# lb_uno_v1_3.net
KiCad netlist of a schematic drawn in EAGLE
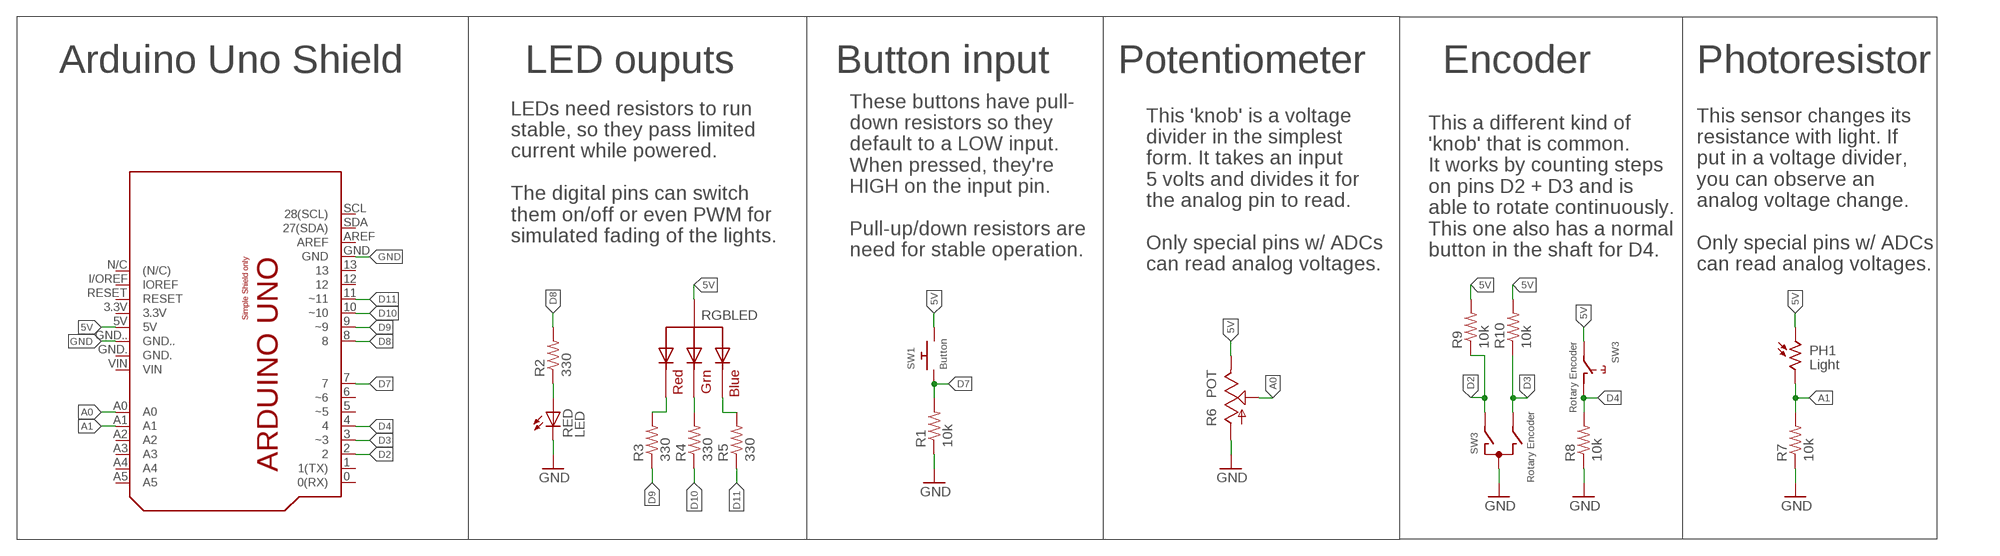
[diagram p0: schematic, sheet 1]

(export (version "E")
  (design (tool "Eeschema 10.0.6"))
  (components
    (comp (ref "PCB1")
      (value "ARDUINO_UNO_V2")
      (footprint "eagle-import:ARDUINO_UNO_V2")
      (libsource (lib "eagle-import") (part "ARDUINO_UNO_V2"))
    )
    (comp (ref "PH1")
      (value "Light")
      (footprint "eagle-import:T0-46-A10XX")
      (libsource (lib "eagle-import") (part "A1060_12"))
    )
    (comp (ref "R1")
      (value "10k")
      (footprint "eagle-import:0207_9")
      (libsource (lib "eagle-import") (part "R-US_0207/9"))
    )
    (comp (ref "R2")
      (value "330")
      (footprint "eagle-import:0207_9")
      (libsource (lib "eagle-import") (part "R-US_0207/9"))
    )
    (comp (ref "R3")
      (value "330")
      (footprint "eagle-import:0207_9")
      (libsource (lib "eagle-import") (part "R-US_0207/9"))
    )
    (comp (ref "R4")
      (value "330")
      (footprint "eagle-import:0207_9")
      (libsource (lib "eagle-import") (part "R-US_0207/9"))
    )
    (comp (ref "R5")
      (value "330")
      (footprint "eagle-import:0207_9")
      (libsource (lib "eagle-import") (part "R-US_0207/9"))
    )
    (comp (ref "R6")
      (value "POT")
      (footprint "eagle-import:B25P")
      (libsource (lib "eagle-import") (part "TRIM_US-B25P"))
    )
    (comp (ref "R7")
      (value "10k")
      (footprint "eagle-import:0207_9")
      (libsource (lib "eagle-import") (part "R-US_0207/9"))
    )
    (comp (ref "R8")
      (value "10k")
      (footprint "eagle-import:0207_9")
      (libsource (lib "eagle-import") (part "R-US_0207/9"))
    )
    (comp (ref "R9")
      (value "10k")
      (footprint "eagle-import:0207_9")
      (libsource (lib "eagle-import") (part "R-US_0207/9"))
    )
    (comp (ref "R10")
      (value "10k")
      (footprint "eagle-import:0207_9")
      (libsource (lib "eagle-import") (part "R-US_0207/9"))
    )
    (comp (ref "RED")
      (value "LED")
      (footprint "eagle-import:5MM")
      (libsource (lib "eagle-import") (part "LED5MM"))
    )
    (comp (ref "RGBLED")
      (value "RGBLED")
      (footprint "eagle-import:LED5MMRGB")
      (libsource (lib "eagle-import") (part "RGBLED_CA-5MM"))
    )
    (comp (ref "SW1")
      (value "Button")
      (footprint "eagle-import:TACT_PANA-EVQ")
      (libsource (lib "eagle-import") (part "SWITCH_PUSHBUTTONEVQ-PE"))
    )
    (comp (ref "SW3")
      (value "Rotary Encoder")
      (footprint "eagle-import:ALPS_EC12E_SW")
      (fields (field (name "MPN") "EC12E2424407"))
      (libsource (lib "eagle-import") (part "EC12E_SW"))
    )
  )
  (nets
    (net (code "1") (name "5V") (class "Default")
      (node (ref "PCB1") (pin "5V") (pinfunction "5V_5V") (pintype "bidirectional"))
      (node (ref "PH1") (pin "1") (pinfunction "1_1") (pintype "passive"))
      (node (ref "R10") (pin "2") (pinfunction "2_2") (pintype "passive"))
      (node (ref "R6") (pin "E") (pinfunction "E_E") (pintype "passive"))
      (node (ref "R9") (pin "2") (pinfunction "2_2") (pintype "passive"))
      (node (ref "RGBLED") (pin "2") (pinfunction "VCC_2") (pintype "bidirectional"))
      (node (ref "SW1") (pin "P$2") (pinfunction "P$2_P$2") (pintype "passive"))
      (node (ref "SW3") (pin "E") (pinfunction "2_E") (pintype "passive"))
    )
    (net (code "2") (name "A0") (class "Default")
      (node (ref "PCB1") (pin "A0") (pinfunction "A0_A0") (pintype "bidirectional"))
      (node (ref "R6") (pin "S") (pinfunction "S_S") (pintype "passive"))
    )
    (net (code "3") (name "A1") (class "Default")
      (node (ref "PCB1") (pin "A1") (pinfunction "A1_A1") (pintype "bidirectional"))
      (node (ref "PH1") (pin "2") (pinfunction "2_2") (pintype "passive"))
      (node (ref "R7") (pin "2") (pinfunction "2_2") (pintype "passive"))
    )
    (net (code "4") (name "D2") (class "Default")
      (node (ref "PCB1") (pin "2") (pinfunction "2_2") (pintype "bidirectional"))
      (node (ref "R9") (pin "1") (pinfunction "1_1") (pintype "passive"))
      (node (ref "SW3") (pin "A") (pinfunction "A_A") (pintype "passive"))
    )
    (net (code "5") (name "D3") (class "Default")
      (node (ref "PCB1") (pin "3") (pinfunction "~{3}_3") (pintype "bidirectional"))
      (node (ref "R10") (pin "1") (pinfunction "1_1") (pintype "passive"))
      (node (ref "SW3") (pin "B") (pinfunction "B_B") (pintype "passive"))
    )
    (net (code "6") (name "D4") (class "Default")
      (node (ref "PCB1") (pin "4") (pinfunction "4_4") (pintype "bidirectional"))
      (node (ref "R8") (pin "2") (pinfunction "2_2") (pintype "passive"))
      (node (ref "SW3") (pin "D") (pinfunction "1_D") (pintype "passive"))
    )
    (net (code "7") (name "D7") (class "Default")
      (node (ref "PCB1") (pin "7") (pinfunction "7_7") (pintype "bidirectional"))
      (node (ref "R1") (pin "2") (pinfunction "2_2") (pintype "passive"))
      (node (ref "SW1") (pin "P$1") (pinfunction "P$1_P$1") (pintype "passive"))
    )
    (net (code "8") (name "D8") (class "Default")
      (node (ref "PCB1") (pin "8") (pinfunction "8_8") (pintype "bidirectional"))
      (node (ref "R2") (pin "2") (pinfunction "2_2") (pintype "passive"))
    )
    (net (code "9") (name "D9") (class "Default")
      (node (ref "PCB1") (pin "9") (pinfunction "~{9}_9") (pintype "bidirectional"))
      (node (ref "R3") (pin "1") (pinfunction "1_1") (pintype "passive"))
    )
    (net (code "10") (name "D10") (class "Default")
      (node (ref "PCB1") (pin "10") (pinfunction "~{10}_10") (pintype "bidirectional"))
      (node (ref "R4") (pin "1") (pinfunction "1_1") (pintype "passive"))
    )
    (net (code "11") (name "D11") (class "Default")
      (node (ref "PCB1") (pin "11") (pinfunction "~{11}_11") (pintype "bidirectional"))
      (node (ref "R5") (pin "1") (pinfunction "1_1") (pintype "passive"))
    )
    (net (code "12") (name "GND") (class "Default")
      (node (ref "PCB1") (pin "GND") (pinfunction "GND_GND") (pintype "bidirectional"))
      (node (ref "PCB1") (pin "GND..") (pinfunction "GND.._GND..") (pintype "bidirectional"))
      (node (ref "R1") (pin "1") (pinfunction "1_1") (pintype "passive"))
      (node (ref "R6") (pin "A") (pinfunction "A_A") (pintype "passive"))
      (node (ref "R7") (pin "1") (pinfunction "1_1") (pintype "passive"))
      (node (ref "R8") (pin "1") (pinfunction "1_1") (pintype "passive"))
      (node (ref "RED") (pin "OUT") (pinfunction "C_OUT") (pintype "passive"))
      (node (ref "SW3") (pin "C") (pinfunction "C_C") (pintype "passive"))
    )
    (net (code "13") (name "Net-(RED-A)") (class "Default")
      (node (ref "R2") (pin "1") (pinfunction "1_1") (pintype "passive"))
      (node (ref "RED") (pin "IN") (pinfunction "A_IN") (pintype "passive"))
    )
    (net (code "14") (name "Net-(RGBLED-BLUE)") (class "Default")
      (node (ref "R5") (pin "2") (pinfunction "2_2") (pintype "passive"))
      (node (ref "RGBLED") (pin "4") (pinfunction "BLUE_4") (pintype "bidirectional"))
    )
    (net (code "15") (name "Net-(RGBLED-GREEN)") (class "Default")
      (node (ref "R4") (pin "2") (pinfunction "2_2") (pintype "passive"))
      (node (ref "RGBLED") (pin "3") (pinfunction "GREEN_3") (pintype "bidirectional"))
    )
    (net (code "16") (name "Net-(RGBLED-RED)") (class "Default")
      (node (ref "R3") (pin "2") (pinfunction "2_2") (pintype "passive"))
      (node (ref "RGBLED") (pin "1") (pinfunction "RED_1") (pintype "bidirectional"))
    )
    (net (code "17") (name "unconnected-(PCB1-(N{slash}C)-PadN{slash}C)") (class "Default")
      (node (ref "PCB1") (pin "N/C") (pinfunction "(N/C)_N/C") (pintype "bidirectional"))
    )
    (net (code "18") (name "unconnected-(PCB1-0(RX)-Pad0)") (class "Default")
      (node (ref "PCB1") (pin "0") (pinfunction "0(RX)_0") (pintype "bidirectional"))
    )
    (net (code "19") (name "unconnected-(PCB1-1(TX)-Pad1)") (class "Default")
      (node (ref "PCB1") (pin "1") (pinfunction "1(TX)_1") (pintype "bidirectional"))
    )
    (net (code "20") (name "unconnected-(PCB1-27(SDA)-PadSDA)") (class "Default")
      (node (ref "PCB1") (pin "SDA") (pinfunction "27(SDA)_SDA") (pintype "bidirectional"))
    )
    (net (code "21") (name "unconnected-(PCB1-28(SCL)-PadSCL)") (class "Default")
      (node (ref "PCB1") (pin "SCL") (pinfunction "28(SCL)_SCL") (pintype "bidirectional"))
    )
    (net (code "22") (name "unconnected-(PCB1-IOREF-PadI{slash}OREF)") (class "Default")
      (node (ref "PCB1") (pin "I/OREF") (pinfunction "IOREF_I/OREF") (pintype "bidirectional"))
    )
    (net (code "23") (name "unconnected-(PCB1-Pad3.3V)") (class "Default")
      (node (ref "PCB1") (pin "3.3V") (pinfunction "3.3V_3.3V") (pintype "bidirectional"))
    )
    (net (code "24") (name "unconnected-(PCB1-Pad12)") (class "Default")
      (node (ref "PCB1") (pin "12") (pinfunction "12_12") (pintype "bidirectional"))
    )
    (net (code "25") (name "unconnected-(PCB1-Pad13)") (class "Default")
      (node (ref "PCB1") (pin "13") (pinfunction "13_13") (pintype "bidirectional"))
    )
    (net (code "26") (name "unconnected-(PCB1-PadA2)") (class "Default")
      (node (ref "PCB1") (pin "A2") (pinfunction "A2_A2") (pintype "bidirectional"))
    )
    (net (code "27") (name "unconnected-(PCB1-PadA3)") (class "Default")
      (node (ref "PCB1") (pin "A3") (pinfunction "A3_A3") (pintype "bidirectional"))
    )
    (net (code "28") (name "unconnected-(PCB1-PadA4)") (class "Default")
      (node (ref "PCB1") (pin "A4") (pinfunction "A4_A4") (pintype "bidirectional"))
    )
    (net (code "29") (name "unconnected-(PCB1-PadA5)") (class "Default")
      (node (ref "PCB1") (pin "A5") (pinfunction "A5_A5") (pintype "bidirectional"))
    )
    (net (code "30") (name "unconnected-(PCB1-PadAREF)") (class "Default")
      (node (ref "PCB1") (pin "AREF") (pinfunction "AREF_AREF") (pintype "bidirectional"))
    )
    (net (code "31") (name "unconnected-(PCB1-PadGND.)") (class "Default")
      (node (ref "PCB1") (pin "GND.") (pinfunction "GND._GND.") (pintype "bidirectional"))
    )
    (net (code "32") (name "unconnected-(PCB1-PadRESET)") (class "Default")
      (node (ref "PCB1") (pin "RESET") (pinfunction "RESET_RESET") (pintype "bidirectional"))
    )
    (net (code "33") (name "unconnected-(PCB1-PadVIN)") (class "Default")
      (node (ref "PCB1") (pin "VIN") (pinfunction "VIN_VIN") (pintype "bidirectional"))
    )
    (net (code "34") (name "unconnected-(PCB1-~{5}-Pad5)") (class "Default")
      (node (ref "PCB1") (pin "5") (pinfunction "~{5}_5") (pintype "bidirectional"))
    )
    (net (code "35") (name "unconnected-(PCB1-~{6}-Pad6)") (class "Default")
      (node (ref "PCB1") (pin "6") (pinfunction "~{6}_6") (pintype "bidirectional"))
    )
  )
)
